# Thunder-Refix.net
KiCad netlist of a schematic drawn in Altium Designer
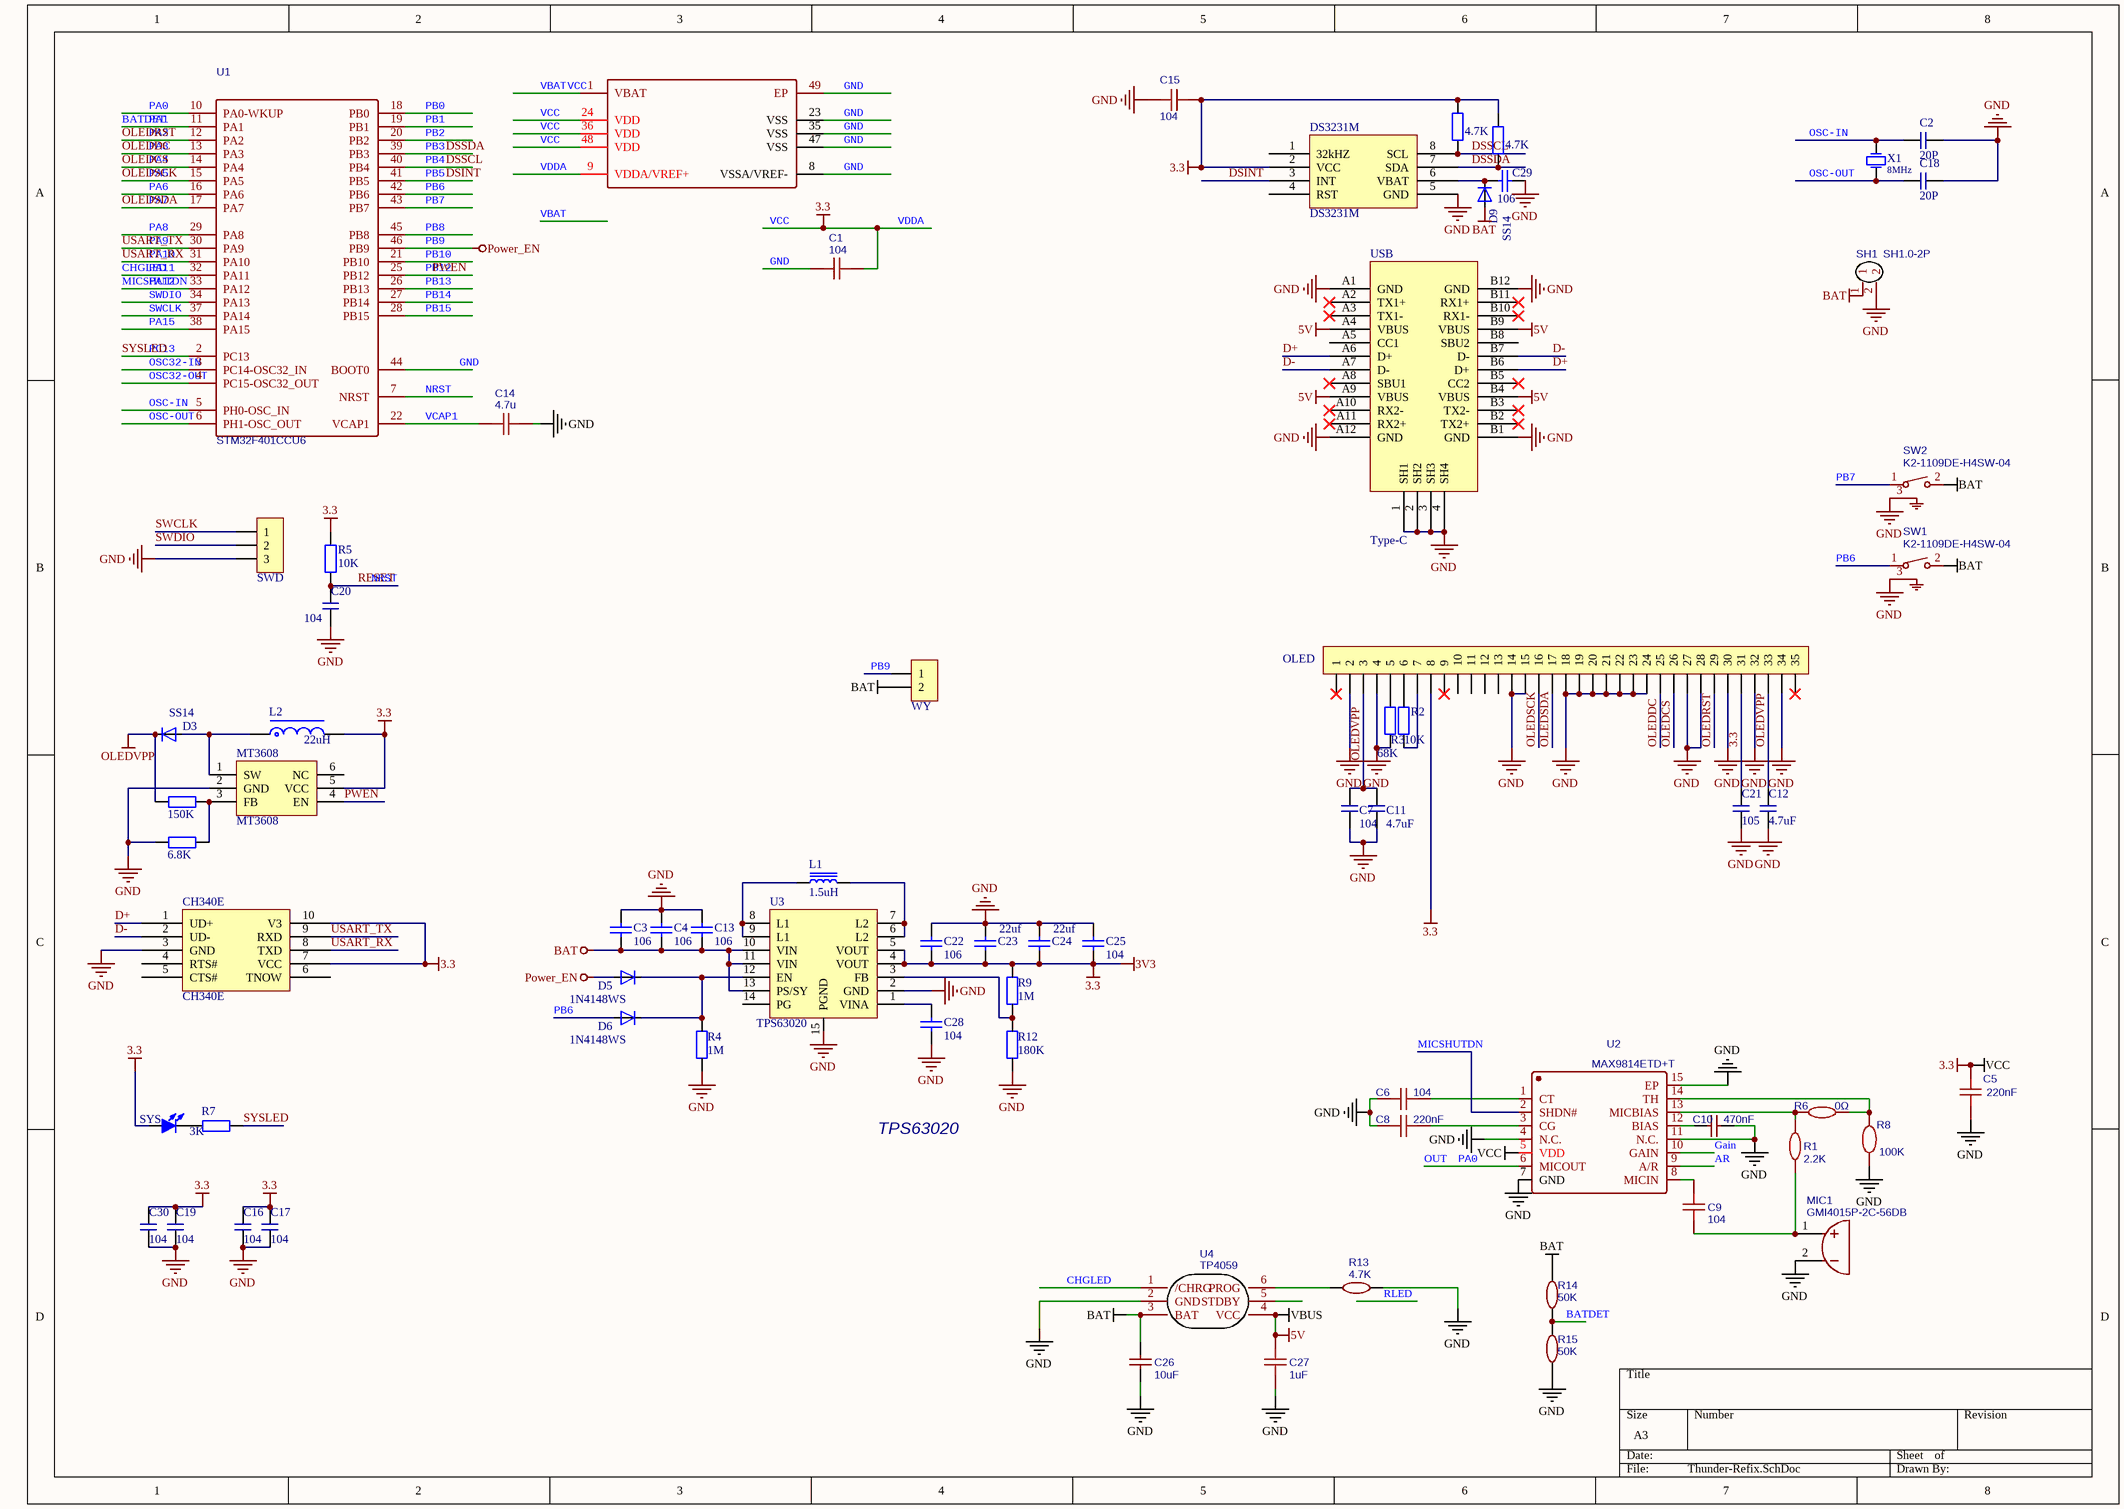
[diagram p0: Thunder-Refix.SchDoc]

(export (version "E")
  (design (tool "Eeschema 10.0.6"))
  (components
    (comp (ref "C1")
      (value "104")
      (footprint "0603C")
      (fields (field (name "CONTRIBUTOR") "LCEDA_Lib"))
      (libsource (lib "altium-import") (part "root_2_0.1u_"))
    )
    (comp (ref "C2") (value "20P") (footprint "0603C") (libsource (lib "Schlib1") (part "电容")))
    (comp (ref "C3")
      (value "106")
      (footprint "我的PCB库:0603c")
      (fields (field (name "C") "106"))
      (libsource (lib "元件库") (part "cap"))
    )
    (comp (ref "C4")
      (value "106")
      (footprint "我的PCB库:0603c")
      (fields (field (name "C") "106"))
      (libsource (lib "元件库") (part "cap"))
    )
    (comp (ref "C5")
      (value "220nF")
      (footprint "0603c")
      (fields
        (field (name "BOM_SUPPLIER PART") "C354366")
        (field (name "BOM_MANUFACTURER PART") "GCJ21BR71H224KA01L")
        (field (name "CONTRIBUTOR") "LCSC")
      )
      (libsource (lib "altium-import") (part "root_1_220nF_"))
    )
    (comp (ref "C6")
      (value "104")
      (footprint "0603c")
      (fields
        (field (name "BOM_SUPPLIER PART") "C444732")
        (field (name "BOM_MANUFACTURER PART") "FS055C104K4Z2A")
        (field (name "CONTRIBUTOR") "LCSC")
      )
      (libsource (lib "altium-import") (part "root_1_100nF_"))
    )
    (comp (ref "C7") (value "104") (footprint "0603C") (libsource (lib "Schlib1") (part "电容")))
    (comp (ref "C8")
      (value "220nF")
      (footprint "0603c")
      (fields
        (field (name "BOM_SUPPLIER PART") "C354366")
        (field (name "BOM_MANUFACTURER PART") "GCJ21BR71H224KA01L")
        (field (name "CONTRIBUTOR") "LCSC")
      )
      (libsource (lib "altium-import") (part "root_0_220nF_"))
    )
    (comp (ref "C9")
      (value "104")
      (footprint "0603c")
      (fields
        (field (name "BOM_SUPPLIER PART") "C444732")
        (field (name "BOM_MANUFACTURER PART") "FS055C104K4Z2A")
        (field (name "CONTRIBUTOR") "LCSC")
      )
      (libsource (lib "altium-import") (part "root_0_100nF_"))
    )
    (comp (ref "C10")
      (value "470nF")
      (footprint "0603c")
      (fields
        (field (name "BOM_MANUFACTURER PART") "CL21B474KBFNNNE")
        (field (name "BOM_SUPPLIER PART") "C13967")
      )
      (libsource (lib "altium-import") (part "root_0_470nF_"))
    )
    (comp (ref "C11") (value "4.7uF") (footprint "0603C") (libsource (lib "Schlib1") (part "电容")))
    (comp (ref "C12") (value "4.7uF") (footprint "0603C") (libsource (lib "Schlib1") (part "电容")))
    (comp (ref "C13")
      (value "106")
      (footprint "0603c")
      (fields (field (name "C") "106"))
      (libsource (lib "元件库") (part "cap"))
    )
    (comp (ref "C14")
      (value "4.7u")
      (footprint "0603C")
      (fields (field (name "CONTRIBUTOR") "LCEDA_Lib"))
      (libsource (lib "altium-import") (part "root_0_4.7u_"))
    )
    (comp (ref "C15")
      (value "104")
      (footprint "0603C")
      (fields (field (name "CONTRIBUTOR") "LCEDA_Lib"))
      (libsource (lib "altium-import") (part "root_2_0.1u_"))
    )
    (comp (ref "C16") (value "104") (footprint "0603C") (libsource (lib "Schlib1") (part "电容")))
    (comp (ref "C17") (value "104") (footprint "0603C") (libsource (lib "Schlib1") (part "电容")))
    (comp (ref "C18") (value "20P") (footprint "0603C") (libsource (lib "Schlib1") (part "电容")))
    (comp (ref "C19") (value "104") (footprint "0603C") (libsource (lib "Schlib1") (part "电容")))
    (comp (ref "C20") (value "104") (footprint "0603C") (libsource (lib "Schlib1") (part "电容")))
    (comp (ref "C21") (value "105") (footprint "0603C") (libsource (lib "Schlib1") (part "电容")))
    (comp (ref "C22")
      (value "106")
      (footprint "0603c")
      (fields (field (name "C") "106"))
      (libsource (lib "元件库") (part "cap"))
    )
    (comp (ref "C23")
      (value "22uf")
      (footprint "0603c")
      (fields (field (name "C") "22uf"))
      (libsource (lib "元件库") (part "cap"))
    )
    (comp (ref "C24")
      (value "22uf")
      (footprint "0603c")
      (fields (field (name "C") "22uf"))
      (libsource (lib "元件库") (part "cap"))
    )
    (comp (ref "C25")
      (value "104")
      (footprint "0603c")
      (fields (field (name "C") "104"))
      (libsource (lib "元件库") (part "cap"))
    )
    (comp (ref "C26")
      (value "10uF")
      (footprint "0603c")
      (fields
        (field (name "BOM_SUPPLIER PART") "C162317")
        (field (name "BOM_MANUFACTURER PART") "GRM21BB31C106KE15L")
        (field (name "CONTRIBUTOR") "LCSC")
      )
      (libsource (lib "altium-import") (part "root_1_10uF_"))
    )
    (comp (ref "C27")
      (value "1uF")
      (footprint "0603c")
      (fields
        (field (name "BOM_SUPPLIER PART") "C319195")
        (field (name "BOM_MANUFACTURER PART") "UMK212BJ105KG-T")
        (field (name "CONTRIBUTOR") "LCSC")
      )
      (libsource (lib "altium-import") (part "root_1_1uF_"))
    )
    (comp (ref "C28")
      (value "104")
      (footprint "0603c")
      (fields (field (name "C") "104"))
      (libsource (lib "元件库") (part "cap"))
    )
    (comp (ref "C29")
      (value "106")
      (footprint "0603c")
      (fields (field (name "C") "106"))
      (libsource (lib "元件库") (part "cap"))
    )
    (comp (ref "C30") (value "104") (footprint "0603C") (libsource (lib "Schlib1") (part "电容")))
    (comp (ref "CH340E") (value "CH340E") (footprint "MSOP10_L") (libsource (lib "CUBE_T1") (part "CH340E")))
    (comp (ref "D3")
      (value "SS14")
      (footprint "SOD323_1N4148WS")
      (description "Diode Switching 75V 0.3A 2-Pin SOD-323 T/R")
      (fields (field (name "MF") "ON Semiconductor") (field (name "MP") "1N4148WS"))
      (libsource (lib "1N4148WS") (part "1N4148WS"))
    )
    (comp (ref "D5")
      (value "1N4148WS")
      (footprint "SOD323_1N4148WS")
      (description "Diode Switching 75V 0.3A 2-Pin SOD-323 T/R")
      (fields (field (name "MF") "ON Semiconductor"))
      (libsource (lib "1N4148WS") (part "1N4148WS"))
    )
    (comp (ref "D6")
      (value "1N4148WS")
      (footprint "SOD323_1N4148WS")
      (description "Diode Switching 75V 0.3A 2-Pin SOD-323 T/R")
      (fields (field (name "MF") "ON Semiconductor"))
      (libsource (lib "1N4148WS") (part "1N4148WS"))
    )
    (comp (ref "D9")
      (value "SS14")
      (footprint "SOD323_1N4148WS")
      (description "Diode Switching 75V 0.3A 2-Pin SOD-323 T/R")
      (fields (field (name "MF") "ON Semiconductor") (field (name "MP") "1N4148WS"))
      (libsource (lib "1N4148WS") (part "1N4148WS"))
    )
    (comp (ref "DS3231M") (value "DS3231M") (footprint "SOP8") (libsource (lib "CUBE_T1") (part "DS3231M")))
    (comp (ref "L1")
      (value "1.5uH")
      (footprint "我的PCB库:IND-SMD_L3.0-W3.0_NR3010")
      (fields (field (name "_VALUE") "1.5uH"))
      (libsource (lib "元件库") (part "Inductor Iron 2"))
    )
    (comp (ref "L2")
      (value "22uH")
      (footprint "IND-SMD_L3.0-W3.0_NR3010")
      (description "功率屏蔽电感")
      (fields (field (name "版权归属") "源创客"))
      (libsource (lib "3.1   - 电阻-电容-电感") (part "L-CDRH"))
    )
    (comp (ref "MIC1")
      (value "GMI4015P-2C-56DB")
      (footprint "MIC-TH_BD4.0-P2.00-D0.4-L-FD")
      (fields
        (field (name "BOM_SUPPLIER PART") "C233299")
        (field (name "BOM_MANUFACTURER PART") "GMI4015P-2C-56db")
        (field (name "CONTRIBUTOR") "LCSC")
      )
      (libsource (lib "altium-import") (part "root_0_GMI4015P-2C-56DB_"))
    )
    (comp (ref "MT3608")
      (value "MT3608")
      (footprint "SOT23-6N")
      (description "可调升压芯片")
      (fields (field (name "版权归属") "源创客"))
      (libsource (lib "1.3   - 电源类芯片") (part "SX1308"))
    )
    (comp (ref "OLED")
      (value "FPC1.0-35P")
      (footprint "1.69 OLED")
      (description "FPC连接器")
      (fields (field (name "版权归属") "源创客"))
      (libsource (lib "4.14 - FPC连接器") (part "FPC-35P"))
    )
    (comp (ref "R1")
      (value "2.2K")
      (footprint "0603r")
      (fields
        (field (name "BOM_SUPPLIER PART") "C325769")
        (field (name "BOM_MANUFACTURER PART") "RMC08052.2K1%N")
        (field (name "CONTRIBUTOR") "LCSC")
      )
      (libsource (lib "altium-import") (part "root_1_2.2K_"))
    )
    (comp (ref "R2")
      (value "10K")
      (footprint "0603R")
      (description "贴片电阻")
      (fields (field (name "版权归属") "源创客"))
      (libsource (lib "3.1   - 电阻-电容-电感") (part "R"))
    )
    (comp (ref "R3")
      (value "68K")
      (footprint "0603R")
      (description "贴片电阻")
      (fields (field (name "版权归属") "源创客"))
      (libsource (lib "3.1   - 电阻-电容-电感") (part "R"))
    )
    (comp (ref "R4")
      (value "1M")
      (footprint "0603r")
      (fields (field (name "R") "1M"))
      (libsource (lib "元件库") (part "Res"))
    )
    (comp (ref "R5")
      (value "10K")
      (footprint "0603R")
      (description "贴片电阻")
      (fields (field (name "版权归属") "源创客"))
      (libsource (lib "3.1   - 电阻-电容-电感") (part "R"))
    )
    (comp (ref "R6")
      (value "0Ω")
      (footprint "0603r")
      (fields
        (field (name "BOM_SUPPLIER PART") "C325765")
        (field (name "BOM_MANUFACTURER PART") "RMC0805150K1%N")
        (field (name "CONTRIBUTOR") "LCSC")
      )
      (libsource (lib "altium-import") (part "root_0_150K_"))
    )
    (comp (ref "R7")
      (value "3K")
      (footprint "0603R")
      (description "贴片电阻")
      (fields (field (name "版权归属") "源创客"))
      (libsource (lib "3.1   - 电阻-电容-电感") (part "R"))
    )
    (comp (ref "R8")
      (value "100K")
      (footprint "0603r")
      (fields
        (field (name "BOM_SUPPLIER PART") "C346756")
        (field (name "BOM_MANUFACTURER PART") "RTAN0805BKE100K")
        (field (name "CONTRIBUTOR") "LCSC")
      )
      (libsource (lib "altium-import") (part "root_1_100K_"))
    )
    (comp (ref "R9")
      (value "1M")
      (footprint "0603r")
      (fields (field (name "R") "1M"))
      (libsource (lib "元件库") (part "Res"))
    )
    (comp (ref "R10")
      (value "4.7K")
      (footprint "0603R")
      (description "贴片电阻")
      (fields (field (name "版权归属") "源创客"))
      (libsource (lib "3.1   - 电阻-电容-电感") (part "R"))
    )
    (comp (ref "R11")
      (value "4.7K")
      (footprint "0603R")
      (description "贴片电阻")
      (fields (field (name "版权归属") "源创客"))
      (libsource (lib "3.1   - 电阻-电容-电感") (part "R"))
    )
    (comp (ref "R12")
      (value "180K")
      (footprint "0603r")
      (fields (field (name "R") "180K"))
      (libsource (lib "元件库") (part "Res"))
    )
    (comp (ref "R13")
      (value "4.7K")
      (footprint "0603r")
      (fields
        (field (name "BOM_MANUFACTURER PART") "RC0603FR-071K5L")
        (field (name "BOM_SUPPLIER PART") "C114668")
      )
      (libsource (lib "altium-import") (part "root_0_1.5K_"))
    )
    (comp (ref "R14")
      (value "50K")
      (footprint "0603r")
      (fields
        (field (name "BOM_MANUFACTURER PART") "RC0603FR-071K5L")
        (field (name "BOM_SUPPLIER PART") "C114668")
      )
      (libsource (lib "altium-import") (part "root_1_1.5K_"))
    )
    (comp (ref "R15")
      (value "50K")
      (footprint "0603r")
      (fields
        (field (name "BOM_MANUFACTURER PART") "RC0603FR-071K5L")
        (field (name "BOM_SUPPLIER PART") "C114668")
      )
      (libsource (lib "altium-import") (part "root_1_1.5K_"))
    )
    (comp (ref "RB")
      (value "150K")
      (footprint "0603R")
      (description "贴片电阻")
      (fields (field (name "版权归属") "源创客"))
      (libsource (lib "3.1   - 电阻-电容-电感") (part "R"))
    )
    (comp (ref "RS")
      (value "6.8K")
      (footprint "0603R")
      (description "贴片电阻")
      (fields (field (name "版权归属") "源创客"))
      (libsource (lib "3.1   - 电阻-电容-电感") (part "R"))
    )
    (comp (ref "SH1")
      (value "SH1.0-2P")
      (footprint "SH1.0-2P")
      (fields (field (name "CONTRIBUTOR") "perry2867"))
      (libsource (lib "altium-import") (part "root_1_SH1.0-2P_"))
    )
    (comp (ref "SW1")
      (value "K2-1109DE-H4SW-04")
      (footprint "KEY-TH_K2-1109DE-CXXW-XX")
      (fields (field (name "BOM_SUPPLIER PART") "C961730") (field (name "CONTRIBUTOR") "LCSC"))
      (libsource (lib "altium-import") (part "root_0_K2-1109DE-H4SW-04_"))
    )
    (comp (ref "SW2")
      (value "K2-1109DE-H4SW-04")
      (footprint "KEY-TH_K2-1109DE-CXXW-XX")
      (fields (field (name "BOM_SUPPLIER PART") "C961730") (field (name "CONTRIBUTOR") "LCSC"))
      (libsource (lib "altium-import") (part "root_0_K2-1109DE-H4SW-04_"))
    )
    (comp (ref "SWD")
      (value "HDR-1X3")
      (footprint "ZH1.5-LI-3P")
      (description "3P接插件")
      (fields (field (name "版权归属") "源创客"))
      (libsource (lib "4.3   - 接插件-脚距1.5") (part "Header 3"))
    )
    (comp (ref "SYS")
      (value "粉色")
      (footprint "0603LED")
      (description "方形LED")
      (fields (field (name "版权归属") "源创客"))
      (libsource (lib "9.1   - LED") (part "LED-F234"))
    )
    (comp (ref "U1")
      (value "STM32F401CCU6")
      (footprint "qfn48")
      (fields (field (name "BOM_SUPPLIER PART") "C79861") (field (name "SUBPART_NO") "1"))
      (libsource (lib "Galaxy") (part "STM32F401CCU6"))
    )
    (comp (ref "U2")
      (value "MAX9814ETD+T")
      (footprint "TDFN-14_L3.0-W3.0-P0.40-BL-EP")
      (fields (field (name "BOM_SUPPLIER PART") "C41714"))
      (libsource (lib "altium-import") (part "root_0_MAX9814ETD+T_"))
    )
    (comp (ref "U3")
      (value "TPS63020")
      (footprint "我的PCB库:TPS63020")
      (libsource (lib "我的元件库") (part "TPS63020"))
    )
    (comp (ref "U4")
      (value "TP4059")
      (footprint "SOT23-6N")
      (fields (field (name "BOM_SUPPLIER PART") "C80364"))
      (libsource (lib "altium-import") (part "root_0_TP4059_"))
    )
    (comp (ref "USB") (value "Type-C") (footprint "Type-C") (libsource (lib "元件") (part "Type-C")))
    (comp (ref "WY")
      (value "HDR-1X2")
      (footprint "MX 1.25-WI-2P")
      (description "2P接插件")
      (fields (field (name "版权归属") "源创客"))
      (libsource (lib "4.2   - 接插件-脚距1.25") (part "Header 2"))
    )
    (comp (ref "X1")
      (value "8MHz")
      (footprint "OSC 5032-2P")
      (description "XTAL,8MHz,±20PPM,12.6*4.5")
      (fields (field (name "Comment") "1.6.1.01.005.001"))
      (libsource (lib "Mark_7") (part "1.6.1.01.005.001"))
    )
  )
  (nets
    (net (code "1") (name "/AR") (class "Default")
      (node (ref "U2") (pin "9") (pinfunction "A/R_9") (pintype "passive"))
    )
    (net (code "2") (name "/BATDET") (class "Default")
      (node (ref "R14") (pin "1") (pinfunction "1_1") (pintype "passive"))
      (node (ref "R15") (pin "2") (pinfunction "2_2") (pintype "passive"))
      (node (ref "U1") (pin "11") (pinfunction "PA1_11") (pintype "passive"))
    )
    (net (code "3") (name "/CHGLED") (class "Default")
      (node (ref "U1") (pin "32") (pinfunction "PA11_32") (pintype "passive"))
      (node (ref "U4") (pin "1") (pinfunction "/CHRG_1") (pintype "passive"))
    )
    (net (code "4") (name "/D+") (class "Default")
      (node (ref "CH340E") (pin "1") (pinfunction "UD+_1") (pintype "passive"))
      (node (ref "USB") (pin "A6") (pinfunction "D+_A6") (pintype "passive"))
      (node (ref "USB") (pin "B6") (pinfunction "D+_B6") (pintype "passive"))
    )
    (net (code "5") (name "/D-") (class "Default")
      (node (ref "CH340E") (pin "2") (pinfunction "UD-_2") (pintype "passive"))
      (node (ref "USB") (pin "A7") (pinfunction "D-_A7") (pintype "passive"))
      (node (ref "USB") (pin "B7") (pinfunction "D-_B7") (pintype "passive"))
    )
    (net (code "6") (name "/DSINT") (class "Default")
      (node (ref "DS3231M") (pin "3") (pinfunction "INT_3") (pintype "passive"))
      (node (ref "U1") (pin "41") (pinfunction "PB5_41") (pintype "passive"))
    )
    (net (code "7") (name "/DSSCL") (class "Default")
      (node (ref "DS3231M") (pin "8") (pinfunction "SCL_8") (pintype "passive"))
      (node (ref "R10") (pin "2") (pinfunction "2_2") (pintype "passive"))
      (node (ref "U1") (pin "40") (pinfunction "PB4_40") (pintype "passive"))
    )
    (net (code "8") (name "/DSSDA") (class "Default")
      (node (ref "DS3231M") (pin "7") (pinfunction "SDA_7") (pintype "passive"))
      (node (ref "R11") (pin "2") (pinfunction "2_2") (pintype "passive"))
      (node (ref "U1") (pin "39") (pinfunction "PB3_39") (pintype "passive"))
    )
    (net (code "9") (name "/Gain") (class "Default")
      (node (ref "U2") (pin "10") (pinfunction "GAIN_10") (pintype "passive"))
    )
    (net (code "10") (name "/MICSHUTDN") (class "Default")
      (node (ref "U1") (pin "33") (pinfunction "PA12_33") (pintype "passive"))
      (node (ref "U2") (pin "2") (pinfunction "SHDN#_2") (pintype "passive"))
    )
    (net (code "11") (name "/NRST") (class "Default")
      (node (ref "C20") (pin "1") (pinfunction "1_1") (pintype "passive"))
      (node (ref "R5") (pin "2") (pinfunction "2_2") (pintype "passive"))
      (node (ref "U1") (pin "7") (pinfunction "NRST_7") (pintype "passive"))
    )
    (net (code "12") (name "/OLEDCS") (class "Default")
      (node (ref "OLED") (pin "26") (pinfunction "26_26") (pintype "passive"))
      (node (ref "U1") (pin "14") (pinfunction "PA4_14") (pintype "passive"))
    )
    (net (code "13") (name "/OLEDDC") (class "Default")
      (node (ref "OLED") (pin "25") (pinfunction "25_25") (pintype "passive"))
      (node (ref "U1") (pin "13") (pinfunction "PA3_13") (pintype "passive"))
    )
    (net (code "14") (name "/OLEDRST") (class "Default")
      (node (ref "OLED") (pin "29") (pinfunction "29_29") (pintype "passive"))
      (node (ref "U1") (pin "12") (pinfunction "PA2_12") (pintype "passive"))
    )
    (net (code "15") (name "/OLEDSCK") (class "Default")
      (node (ref "OLED") (pin "16") (pinfunction "16_16") (pintype "passive"))
      (node (ref "U1") (pin "15") (pinfunction "PA5_15") (pintype "passive"))
    )
    (net (code "16") (name "/OLEDSDA") (class "Default")
      (node (ref "OLED") (pin "17") (pinfunction "17_17") (pintype "passive"))
      (node (ref "U1") (pin "17") (pinfunction "PA7_17") (pintype "passive"))
    )
    (net (code "17") (name "/OSC-IN") (class "Default")
      (node (ref "C2") (pin "2") (pinfunction "2_2") (pintype "passive"))
      (node (ref "U1") (pin "5") (pinfunction "PH0-OSC_IN_5") (pintype "passive"))
      (node (ref "X1") (pin "1") (pinfunction "OSC1_1") (pintype "passive"))
    )
    (net (code "18") (name "/OSC-OUT") (class "Default")
      (node (ref "C18") (pin "2") (pinfunction "2_2") (pintype "passive"))
      (node (ref "U1") (pin "6") (pinfunction "PH1-OSC_OUT_6") (pintype "passive"))
      (node (ref "X1") (pin "2") (pinfunction "OSC2_2") (pintype "passive"))
    )
    (net (code "19") (name "/OSC32-IN") (class "Default")
      (node (ref "U1") (pin "3") (pinfunction "PC14-OSC32_IN_3") (pintype "passive"))
    )
    (net (code "20") (name "/OSC32-OUT") (class "Default")
      (node (ref "U1") (pin "4") (pinfunction "PC15-OSC32_OUT_4") (pintype "passive"))
    )
    (net (code "21") (name "/OUT") (class "Default")
      (node (ref "U1") (pin "10") (pinfunction "PA0-WKUP_10") (pintype "passive"))
      (node (ref "U2") (pin "6") (pinfunction "MICOUT_6") (pintype "passive"))
    )
    (net (code "22") (name "/PA6") (class "Default")
      (node (ref "U1") (pin "16") (pinfunction "PA6_16") (pintype "passive"))
    )
    (net (code "23") (name "/PA8") (class "Default")
      (node (ref "U1") (pin "29") (pinfunction "PA8_29") (pintype "passive"))
    )
    (net (code "24") (name "/PA9") (class "Default")
      (node (ref "CH340E") (pin "9") (pinfunction "RXD_9") (pintype "passive"))
      (node (ref "U1") (pin "30") (pinfunction "PA9_30") (pintype "passive"))
    )
    (net (code "25") (name "/PA10") (class "Default")
      (node (ref "CH340E") (pin "8") (pinfunction "TXD_8") (pintype "passive"))
      (node (ref "U1") (pin "31") (pinfunction "PA10_31") (pintype "passive"))
    )
    (net (code "26") (name "/PA15") (class "Default")
      (node (ref "U1") (pin "38") (pinfunction "PA15_38") (pintype "passive"))
    )
    (net (code "27") (name "/PB0") (class "Default")
      (node (ref "U1") (pin "18") (pinfunction "PB0_18") (pintype "passive"))
    )
    (net (code "28") (name "/PB1") (class "Default")
      (node (ref "U1") (pin "19") (pinfunction "PB1_19") (pintype "passive"))
    )
    (net (code "29") (name "/PB2") (class "Default")
      (node (ref "U1") (pin "20") (pinfunction "PB2_20") (pintype "passive"))
    )
    (net (code "30") (name "/PB6") (class "Default")
      (node (ref "D6") (pin "A") (pinfunction "A_A") (pintype "passive"))
      (node (ref "SW1") (pin "1") (pinfunction "1_1") (pintype "passive"))
      (node (ref "U1") (pin "42") (pinfunction "PB6_42") (pintype "passive"))
    )
    (net (code "31") (name "/PB7") (class "Default")
      (node (ref "SW2") (pin "1") (pinfunction "1_1") (pintype "passive"))
      (node (ref "U1") (pin "43") (pinfunction "PB7_43") (pintype "passive"))
    )
    (net (code "32") (name "/PB8") (class "Default")
      (node (ref "U1") (pin "45") (pinfunction "PB8_45") (pintype "passive"))
    )
    (net (code "33") (name "/PB10") (class "Default")
      (node (ref "U1") (pin "21") (pinfunction "PB10_21") (pintype "passive"))
    )
    (net (code "34") (name "/PB12") (class "Default")
      (node (ref "MT3608") (pin "4") (pinfunction "EN_4") (pintype "passive"))
      (node (ref "U1") (pin "25") (pinfunction "PB12_25") (pintype "passive"))
    )
    (net (code "35") (name "/PB13") (class "Default")
      (node (ref "U1") (pin "26") (pinfunction "PB13_26") (pintype "passive"))
    )
    (net (code "36") (name "/PB14") (class "Default")
      (node (ref "U1") (pin "27") (pinfunction "PB14_27") (pintype "passive"))
    )
    (net (code "37") (name "/PB15") (class "Default")
      (node (ref "U1") (pin "28") (pinfunction "PB15_28") (pintype "passive"))
    )
    (net (code "38") (name "/PC13") (class "Default")
      (node (ref "R7") (pin "1") (pinfunction "1_1") (pintype "passive"))
      (node (ref "U1") (pin "2") (pinfunction "PC13_2") (pintype "passive"))
    )
    (net (code "40") (name "/SWCLK") (class "Default")
      (node (ref "SWD") (pin "1") (pinfunction "1_1") (pintype "passive"))
      (node (ref "U1") (pin "37") (pinfunction "PA14_37") (pintype "passive"))
    )
    (net (code "41") (name "/SWDIO") (class "Default")
      (node (ref "SWD") (pin "2") (pinfunction "2_2") (pintype "passive"))
      (node (ref "U1") (pin "34") (pinfunction "PA13_34") (pintype "passive"))
    )
    (net (code "42") (name "/VCAP1") (class "Default")
      (node (ref "C14") (pin "1") (pinfunction "1_1") (pintype "passive"))
      (node (ref "U1") (pin "22") (pinfunction "VCAP1_22") (pintype "passive"))
    )
    (net (code "43") (name "3.3") (class "Default")
      (node (ref "C1") (pin "1") (pinfunction "1_1") (pintype "passive"))
      (node (ref "C15") (pin "1") (pinfunction "1_1") (pintype "passive"))
      (node (ref "C16") (pin "1") (pinfunction "1_1") (pintype "passive"))
      (node (ref "C17") (pin "1") (pinfunction "1_1") (pintype "passive"))
      (node (ref "C19") (pin "1") (pinfunction "1_1") (pintype "passive"))
      (node (ref "C21") (pin "1") (pinfunction "1_1") (pintype "passive"))
      (node (ref "C22") (pin "1") (pinfunction "1_1") (pintype "passive"))
      (node (ref "C23") (pin "1") (pinfunction "1_1") (pintype "passive"))
      (node (ref "C24") (pin "1") (pinfunction "1_1") (pintype "passive"))
      (node (ref "C25") (pin "1") (pinfunction "1_1") (pintype "passive"))
      (node (ref "C30") (pin "1") (pinfunction "1_1") (pintype "passive"))
      (node (ref "C5") (pin "2") (pinfunction "2_2") (pintype "passive"))
      (node (ref "CH340E") (pin "10") (pinfunction "V3_10") (pintype "passive"))
      (node (ref "CH340E") (pin "7") (pinfunction "VCC_7") (pintype "passive"))
      (node (ref "DS3231M") (pin "2") (pinfunction "VCC_2") (pintype "passive"))
      (node (ref "L2") (pin "2") (pinfunction "2_2") (pintype "passive"))
      (node (ref "MT3608") (pin "5") (pinfunction "VCC_5") (pintype "passive"))
      (node (ref "OLED") (pin "31") (pinfunction "31_31") (pintype "passive"))
      (node (ref "OLED") (pin "8") (pinfunction "8_8") (pintype "passive"))
      (node (ref "R10") (pin "1") (pinfunction "1_1") (pintype "passive"))
      (node (ref "R11") (pin "1") (pinfunction "1_1") (pintype "passive"))
      (node (ref "R5") (pin "1") (pinfunction "1_1") (pintype "passive"))
      (node (ref "R9") (pin "1") (pinfunction "1_1") (pintype "passive"))
      (node (ref "SYS") (pin "1") (pinfunction "A_1") (pintype "passive"))
      (node (ref "U1") (pin "1") (pinfunction "VBAT_1") (pintype "passive"))
      (node (ref "U1") (pin "24") (pinfunction "VDD_24") (pintype "passive"))
      (node (ref "U1") (pin "36") (pinfunction "VDD_36") (pintype "passive"))
      (node (ref "U1") (pin "48") (pinfunction "VDD_48") (pintype "passive"))
      (node (ref "U1") (pin "9") (pinfunction "VDDA/VREF+_9") (pintype "passive"))
      (node (ref "U2") (pin "5") (pinfunction "VDD_5") (pintype "passive"))
      (node (ref "U3") (pin "4") (pinfunction "VOUT_4") (pintype "passive"))
      (node (ref "U3") (pin "5") (pinfunction "VOUT_5") (pintype "passive"))
    )
    (net (code "44") (name "5V") (class "Default")
      (node (ref "C27") (pin "1") (pinfunction "1_1") (pintype "passive"))
      (node (ref "U4") (pin "4") (pinfunction "VCC_4") (pintype "passive"))
      (node (ref "USB") (pin "A4") (pinfunction "VBUS_A4") (pintype "passive"))
      (node (ref "USB") (pin "A9") (pinfunction "VBUS_A9") (pintype "passive"))
      (node (ref "USB") (pin "B4") (pinfunction "VBUS_B4") (pintype "passive"))
      (node (ref "USB") (pin "B9") (pinfunction "VBUS_B9") (pintype "passive"))
    )
    (net (code "45") (name "BAT") (class "Default")
      (node (ref "C13") (pin "1") (pinfunction "1_1") (pintype "passive"))
      (node (ref "C26") (pin "2") (pinfunction "2_2") (pintype "passive"))
      (node (ref "C3") (pin "1") (pinfunction "1_1") (pintype "passive"))
      (node (ref "C4") (pin "1") (pinfunction "1_1") (pintype "passive"))
      (node (ref "D9") (pin "A") (pinfunction "A_A") (pintype "passive"))
      (node (ref "R14") (pin "2") (pinfunction "2_2") (pintype "passive"))
      (node (ref "SH1") (pin "1") (pinfunction "1_1") (pintype "passive"))
      (node (ref "SW1") (pin "2") (pinfunction "2_2") (pintype "passive"))
      (node (ref "SW2") (pin "2") (pinfunction "2_2") (pintype "passive"))
      (node (ref "U3") (pin "10") (pinfunction "VIN_10") (pintype "passive"))
      (node (ref "U3") (pin "11") (pinfunction "VIN_11") (pintype "passive"))
      (node (ref "U3") (pin "13") (pinfunction "PS/SY_13") (pintype "passive"))
      (node (ref "U4") (pin "3") (pinfunction "BAT_3") (pintype "passive"))
      (node (ref "WY") (pin "2") (pinfunction "2_2") (pintype "passive"))
    )
    (net (code "46") (name "GND") (class "Default")
      (node (ref "C1") (pin "2") (pinfunction "2_2") (pintype "passive"))
      (node (ref "C10") (pin "2") (pinfunction "2_2") (pintype "passive"))
      (node (ref "C11") (pin "2") (pinfunction "2_2") (pintype "passive"))
      (node (ref "C12") (pin "2") (pinfunction "2_2") (pintype "passive"))
      (node (ref "C13") (pin "2") (pinfunction "2_2") (pintype "passive"))
      (node (ref "C14") (pin "2") (pinfunction "2_2") (pintype "passive"))
      (node (ref "C15") (pin "2") (pinfunction "2_2") (pintype "passive"))
      (node (ref "C16") (pin "2") (pinfunction "2_2") (pintype "passive"))
      (node (ref "C17") (pin "2") (pinfunction "2_2") (pintype "passive"))
      (node (ref "C18") (pin "1") (pinfunction "1_1") (pintype "passive"))
      (node (ref "C19") (pin "2") (pinfunction "2_2") (pintype "passive"))
      (node (ref "C2") (pin "1") (pinfunction "1_1") (pintype "passive"))
      (node (ref "C20") (pin "2") (pinfunction "2_2") (pintype "passive"))
      (node (ref "C21") (pin "2") (pinfunction "2_2") (pintype "passive"))
      (node (ref "C22") (pin "2") (pinfunction "2_2") (pintype "passive"))
      (node (ref "C23") (pin "2") (pinfunction "2_2") (pintype "passive"))
      (node (ref "C24") (pin "2") (pinfunction "2_2") (pintype "passive"))
      (node (ref "C25") (pin "2") (pinfunction "2_2") (pintype "passive"))
      (node (ref "C26") (pin "1") (pinfunction "1_1") (pintype "passive"))
      (node (ref "C27") (pin "2") (pinfunction "2_2") (pintype "passive"))
      (node (ref "C28") (pin "1") (pinfunction "1_1") (pintype "passive"))
      (node (ref "C29") (pin "1") (pinfunction "1_1") (pintype "passive"))
      (node (ref "C3") (pin "2") (pinfunction "2_2") (pintype "passive"))
      (node (ref "C30") (pin "2") (pinfunction "2_2") (pintype "passive"))
      (node (ref "C4") (pin "2") (pinfunction "2_2") (pintype "passive"))
      (node (ref "C5") (pin "1") (pinfunction "1_1") (pintype "passive"))
      (node (ref "C6") (pin "1") (pinfunction "1_1") (pintype "passive"))
      (node (ref "C7") (pin "2") (pinfunction "2_2") (pintype "passive"))
      (node (ref "C8") (pin "1") (pinfunction "1_1") (pintype "passive"))
      (node (ref "CH340E") (pin "3") (pinfunction "GND_3") (pintype "passive"))
      (node (ref "DS3231M") (pin "5") (pinfunction "GND_5") (pintype "passive"))
      (node (ref "MIC1") (pin "2") (pinfunction "2_2") (pintype "passive"))
      (node (ref "MT3608") (pin "2") (pinfunction "GND_2") (pintype "passive"))
      (node (ref "OLED") (pin "14") (pinfunction "14_14") (pintype "passive"))
      (node (ref "OLED") (pin "15") (pinfunction "15_15") (pintype "passive"))
      (node (ref "OLED") (pin "18") (pinfunction "18_18") (pintype "passive"))
      (node (ref "OLED") (pin "19") (pinfunction "19_19") (pintype "passive"))
      (node (ref "OLED") (pin "2") (pinfunction "2_2") (pintype "passive"))
      (node (ref "OLED") (pin "20") (pinfunction "20_20") (pintype "passive"))
      (node (ref "OLED") (pin "21") (pinfunction "21_21") (pintype "passive"))
      (node (ref "OLED") (pin "22") (pinfunction "22_22") (pintype "passive"))
      (node (ref "OLED") (pin "23") (pinfunction "23_23") (pintype "passive"))
      (node (ref "OLED") (pin "24") (pinfunction "24_24") (pintype "passive"))
      (node (ref "OLED") (pin "27") (pinfunction "27_27") (pintype "passive"))
      (node (ref "OLED") (pin "28") (pinfunction "28_28") (pintype "passive"))
      (node (ref "OLED") (pin "30") (pinfunction "30_30") (pintype "passive"))
      (node (ref "OLED") (pin "32") (pinfunction "32_32") (pintype "passive"))
      (node (ref "OLED") (pin "34") (pinfunction "34_34") (pintype "passive"))
      (node (ref "OLED") (pin "4") (pinfunction "4_4") (pintype "passive"))
      (node (ref "R12") (pin "2") (pinfunction "2_2") (pintype "passive"))
      (node (ref "R13") (pin "2") (pinfunction "2_2") (pintype "passive"))
      (node (ref "R15") (pin "1") (pinfunction "1_1") (pintype "passive"))
      (node (ref "R3") (pin "1") (pinfunction "1_1") (pintype "passive"))
      (node (ref "R4") (pin "2") (pinfunction "2_2") (pintype "passive"))
      (node (ref "R8") (pin "1") (pinfunction "1_1") (pintype "passive"))
      (node (ref "RS") (pin "1") (pinfunction "1_1") (pintype "passive"))
      (node (ref "SH1") (pin "2") (pinfunction "2_2") (pintype "passive"))
      (node (ref "SW1") (pin "3") (pinfunction "GND_3") (pintype "passive"))
      (node (ref "SW2") (pin "3") (pinfunction "GND_3") (pintype "passive"))
      (node (ref "SWD") (pin "3") (pinfunction "3_3") (pintype "passive"))
      (node (ref "U1") (pin "23") (pinfunction "VSS_23") (pintype "passive"))
      (node (ref "U1") (pin "35") (pinfunction "VSS_35") (pintype "passive"))
      (node (ref "U1") (pin "44") (pinfunction "BOOT0_44") (pintype "passive"))
      (node (ref "U1") (pin "47") (pinfunction "VSS_47") (pintype "passive"))
      (node (ref "U1") (pin "49") (pinfunction "EP_49") (pintype "passive"))
      (node (ref "U1") (pin "8") (pinfunction "VSSA/VREF-_8") (pintype "passive"))
      (node (ref "U2") (pin "11") (pinfunction "N.C._11") (pintype "passive"))
      (node (ref "U2") (pin "15") (pinfunction "EP_15") (pintype "passive"))
      (node (ref "U2") (pin "4") (pinfunction "N.C._4") (pintype "passive"))
      (node (ref "U2") (pin "7") (pinfunction "GND_7") (pintype "passive"))
      (node (ref "U3") (pin "15") (pinfunction "PGND_15") (pintype "passive"))
      (node (ref "U3") (pin "2") (pinfunction "GND_2") (pintype "passive"))
      (node (ref "U4") (pin "2") (pinfunction "GND_2") (pintype "passive"))
      (node (ref "USB") (pin "1") (pinfunction "SH1_1") (pintype "passive"))
      (node (ref "USB") (pin "2") (pinfunction "SH2_2") (pintype "passive"))
      (node (ref "USB") (pin "3") (pinfunction "SH3_3") (pintype "passive"))
      (node (ref "USB") (pin "4") (pinfunction "SH4_4") (pintype "passive"))
      (node (ref "USB") (pin "A1") (pinfunction "GND_A1") (pintype "passive"))
      (node (ref "USB") (pin "A12") (pinfunction "GND_A12") (pintype "passive"))
      (node (ref "USB") (pin "B1") (pinfunction "GND_B1") (pintype "passive"))
      (node (ref "USB") (pin "B12") (pinfunction "GND_B12") (pintype "passive"))
    )
    (net (code "47") (name "Net-(C9-Pad2)") (class "Default")
      (node (ref "C9") (pin "2") (pinfunction "2_2") (pintype "passive"))
      (node (ref "MIC1") (pin "1") (pinfunction "1_1") (pintype "passive"))
      (node (ref "R1") (pin "1") (pinfunction "1_1") (pintype "passive"))
    )
    (net (code "48") (name "Net-(DS3231M-VBAT)") (class "Default")
      (node (ref "C29") (pin "2") (pinfunction "2_2") (pintype "passive"))
      (node (ref "D9") (pin "C") (pinfunction "C_C") (pintype "passive"))
      (node (ref "DS3231M") (pin "6") (pinfunction "VBAT_6") (pintype "passive"))
    )
    (net (code "49") (name "Net-(L1-Pad1)") (class "Default")
      (node (ref "L1") (pin "1") (pinfunction "1_1") (pintype "passive"))
      (node (ref "U3") (pin "8") (pinfunction "L1_8") (pintype "passive"))
      (node (ref "U3") (pin "9") (pinfunction "L1_9") (pintype "passive"))
    )
    (net (code "50") (name "Net-(L1-Pad2)") (class "Default")
      (node (ref "L1") (pin "2") (pinfunction "2_2") (pintype "passive"))
      (node (ref "U3") (pin "6") (pinfunction "L2_6") (pintype "passive"))
      (node (ref "U3") (pin "7") (pinfunction "L2_7") (pintype "passive"))
    )
    (net (code "51") (name "Net-(MT3608-FB)") (class "Default")
      (node (ref "MT3608") (pin "3") (pinfunction "FB_3") (pintype "passive"))
      (node (ref "RB") (pin "2") (pinfunction "2_2") (pintype "passive"))
      (node (ref "RS") (pin "2") (pinfunction "2_2") (pintype "passive"))
    )
    (net (code "52") (name "Net-(MT3608-SW)") (class "Default")
      (node (ref "D3") (pin "A") (pinfunction "A_A") (pintype "passive"))
      (node (ref "L2") (pin "1") (pinfunction "1_1") (pintype "passive"))
      (node (ref "MT3608") (pin "1") (pinfunction "SW_1") (pintype "passive"))
    )
    (net (code "53") (name "Net-(OLED-Pad5)") (class "Default")
      (node (ref "OLED") (pin "5") (pinfunction "5_5") (pintype "passive"))
      (node (ref "R3") (pin "2") (pinfunction "2_2") (pintype "passive"))
    )
    (net (code "54") (name "Net-(OLED-Pad6)") (class "Default")
      (node (ref "OLED") (pin "6") (pinfunction "6_6") (pintype "passive"))
      (node (ref "R2") (pin "2") (pinfunction "2_2") (pintype "passive"))
    )
    (net (code "55") (name "Net-(OLED-Pad7)") (class "Default")
      (node (ref "OLED") (pin "7") (pinfunction "7_7") (pintype "passive"))
      (node (ref "R2") (pin "1") (pinfunction "1_1") (pintype "passive"))
    )
    (net (code "56") (name "Net-(SYS-K)") (class "Default")
      (node (ref "R7") (pin "2") (pinfunction "2_2") (pintype "passive"))
      (node (ref "SYS") (pin "2") (pinfunction "K_2") (pintype "passive"))
    )
    (net (code "57") (name "Net-(U2-BIAS)") (class "Default")
      (node (ref "C10") (pin "1") (pinfunction "1_1") (pintype "passive"))
      (node (ref "U2") (pin "12") (pinfunction "BIAS_12") (pintype "passive"))
    )
    (net (code "58") (name "Net-(U2-CG)") (class "Default")
      (node (ref "C8") (pin "2") (pinfunction "2_2") (pintype "passive"))
      (node (ref "U2") (pin "3") (pinfunction "CG_3") (pintype "passive"))
    )
    (net (code "59") (name "Net-(U2-CT)") (class "Default")
      (node (ref "C6") (pin "2") (pinfunction "2_2") (pintype "passive"))
      (node (ref "U2") (pin "1") (pinfunction "CT_1") (pintype "passive"))
    )
    (net (code "60") (name "Net-(U2-MICBIAS)") (class "Default")
      (node (ref "R1") (pin "2") (pinfunction "2_2") (pintype "passive"))
      (node (ref "R6") (pin "1") (pinfunction "1_1") (pintype "passive"))
      (node (ref "U2") (pin "13") (pinfunction "MICBIAS_13") (pintype "passive"))
    )
    (net (code "61") (name "Net-(U2-MICIN)") (class "Default")
      (node (ref "C9") (pin "1") (pinfunction "1_1") (pintype "passive"))
      (node (ref "U2") (pin "8") (pinfunction "MICIN_8") (pintype "passive"))
    )
    (net (code "62") (name "Net-(U2-TH)") (class "Default")
      (node (ref "R6") (pin "2") (pinfunction "2_2") (pintype "passive"))
      (node (ref "R8") (pin "2") (pinfunction "2_2") (pintype "passive"))
      (node (ref "U2") (pin "14") (pinfunction "TH_14") (pintype "passive"))
    )
    (net (code "63") (name "Net-(U3-EN)") (class "Default")
      (node (ref "D5") (pin "C") (pinfunction "C_C") (pintype "passive"))
      (node (ref "D6") (pin "C") (pinfunction "C_C") (pintype "passive"))
      (node (ref "R4") (pin "1") (pinfunction "1_1") (pintype "passive"))
      (node (ref "U3") (pin "12") (pinfunction "EN_12") (pintype "passive"))
    )
    (net (code "64") (name "Net-(U3-FB)") (class "Default")
      (node (ref "R12") (pin "1") (pinfunction "1_1") (pintype "passive"))
      (node (ref "R9") (pin "2") (pinfunction "2_2") (pintype "passive"))
      (node (ref "U3") (pin "3") (pinfunction "FB_3") (pintype "passive"))
    )
    (net (code "65") (name "Net-(U3-VINA)") (class "Default")
      (node (ref "C28") (pin "2") (pinfunction "2_2") (pintype "passive"))
      (node (ref "U3") (pin "1") (pinfunction "VINA_1") (pintype "passive"))
    )
    (net (code "66") (name "Net-(U4-PROG)") (class "Default")
      (node (ref "R13") (pin "1") (pinfunction "1_1") (pintype "passive"))
      (node (ref "U4") (pin "6") (pinfunction "PROG_6") (pintype "passive"))
    )
    (net (code "67") (name "OLEDVPP") (class "Default")
      (node (ref "C11") (pin "1") (pinfunction "1_1") (pintype "passive"))
      (node (ref "C12") (pin "1") (pinfunction "1_1") (pintype "passive"))
      (node (ref "C7") (pin "1") (pinfunction "1_1") (pintype "passive"))
      (node (ref "D3") (pin "C") (pinfunction "C_C") (pintype "passive"))
      (node (ref "OLED") (pin "3") (pinfunction "3_3") (pintype "passive"))
      (node (ref "OLED") (pin "33") (pinfunction "33_33") (pintype "passive"))
      (node (ref "RB") (pin "1") (pinfunction "1_1") (pintype "passive"))
    )
    (net (code "68") (name "Power_EN") (class "Default")
      (node (ref "D5") (pin "A") (pinfunction "A_A") (pintype "passive"))
      (node (ref "U1") (pin "46") (pinfunction "PB9_46") (pintype "passive"))
      (node (ref "WY") (pin "1") (pinfunction "1_1") (pintype "passive"))
    )
    (net (code "69") (name "unconnected-(CH340E-CTS#-Pad5)") (class "Default")
      (node (ref "CH340E") (pin "5") (pinfunction "CTS#_5") (pintype "passive"))
    )
    (net (code "70") (name "unconnected-(CH340E-RTS#-Pad4)") (class "Default")
      (node (ref "CH340E") (pin "4") (pinfunction "RTS#_4") (pintype "passive"))
    )
    (net (code "71") (name "unconnected-(CH340E-TNOW-Pad6)") (class "Default")
      (node (ref "CH340E") (pin "6") (pinfunction "TNOW_6") (pintype "passive"))
    )
    (net (code "72") (name "unconnected-(DS3231M-32kHZ-Pad1)") (class "Default")
      (node (ref "DS3231M") (pin "1") (pinfunction "32kHZ_1") (pintype "passive"))
    )
    (net (code "73") (name "unconnected-(DS3231M-RST-Pad4)") (class "Default")
      (node (ref "DS3231M") (pin "4") (pinfunction "RST_4") (pintype "passive"))
    )
    (net (code "74") (name "unconnected-(MT3608-NC-Pad6)") (class "Default")
      (node (ref "MT3608") (pin "6") (pinfunction "NC_6") (pintype "passive"))
    )
    (net (code "75") (name "unconnected-(OLED-Pad1)") (class "Default")
      (node (ref "OLED") (pin "1") (pinfunction "1_1") (pintype "passive+no_connect"))
    )
    (net (code "76") (name "unconnected-(OLED-Pad9)") (class "Default")
      (node (ref "OLED") (pin "9") (pinfunction "9_9") (pintype "passive+no_connect"))
    )
    (net (code "77") (name "unconnected-(OLED-Pad10)") (class "Default")
      (node (ref "OLED") (pin "10") (pinfunction "10_10") (pintype "passive"))
    )
    (net (code "78") (name "unconnected-(OLED-Pad11)") (class "Default")
      (node (ref "OLED") (pin "11") (pinfunction "11_11") (pintype "passive"))
    )
    (net (code "79") (name "unconnected-(OLED-Pad12)") (class "Default")
      (node (ref "OLED") (pin "12") (pinfunction "12_12") (pintype "passive"))
    )
    (net (code "80") (name "unconnected-(OLED-Pad13)") (class "Default")
      (node (ref "OLED") (pin "13") (pinfunction "13_13") (pintype "passive"))
    )
    (net (code "81") (name "unconnected-(OLED-Pad35)") (class "Default")
      (node (ref "OLED") (pin "35") (pinfunction "35_35") (pintype "passive+no_connect"))
    )
    (net (code "82") (name "unconnected-(U3-PG-Pad14)") (class "Default")
      (node (ref "U3") (pin "14") (pinfunction "PG_14") (pintype "passive"))
    )
    (net (code "83") (name "unconnected-(U4-STDBY-Pad5)") (class "Default")
      (node (ref "U4") (pin "5") (pinfunction "STDBY_5") (pintype "passive"))
    )
    (net (code "84") (name "unconnected-(USB-CC1-PadA5)") (class "Default")
      (node (ref "USB") (pin "A5") (pinfunction "CC1_A5") (pintype "passive"))
    )
    (net (code "85") (name "unconnected-(USB-CC2-PadB5)") (class "Default")
      (node (ref "USB") (pin "B5") (pinfunction "CC2_B5") (pintype "passive+no_connect"))
    )
    (net (code "86") (name "unconnected-(USB-RX1+-PadB11)") (class "Default")
      (node (ref "USB") (pin "B11") (pinfunction "RX1+_B11") (pintype "passive+no_connect"))
    )
    (net (code "87") (name "unconnected-(USB-RX1--PadB10)") (class "Default")
      (node (ref "USB") (pin "B10") (pinfunction "RX1-_B10") (pintype "passive+no_connect"))
    )
    (net (code "88") (name "unconnected-(USB-RX2+-PadA11)") (class "Default")
      (node (ref "USB") (pin "A11") (pinfunction "RX2+_A11") (pintype "passive+no_connect"))
    )
    (net (code "89") (name "unconnected-(USB-RX2--PadA10)") (class "Default")
      (node (ref "USB") (pin "A10") (pinfunction "RX2-_A10") (pintype "passive+no_connect"))
    )
    (net (code "90") (name "unconnected-(USB-SBU1-PadA8)") (class "Default")
      (node (ref "USB") (pin "A8") (pinfunction "SBU1_A8") (pintype "passive+no_connect"))
    )
    (net (code "91") (name "unconnected-(USB-SBU2-PadB8)") (class "Default")
      (node (ref "USB") (pin "B8") (pinfunction "SBU2_B8") (pintype "passive"))
    )
    (net (code "92") (name "unconnected-(USB-TX1+-PadA2)") (class "Default")
      (node (ref "USB") (pin "A2") (pinfunction "TX1+_A2") (pintype "passive+no_connect"))
    )
    (net (code "93") (name "unconnected-(USB-TX1--PadA3)") (class "Default")
      (node (ref "USB") (pin "A3") (pinfunction "TX1-_A3") (pintype "passive+no_connect"))
    )
    (net (code "94") (name "unconnected-(USB-TX2+-PadB2)") (class "Default")
      (node (ref "USB") (pin "B2") (pinfunction "TX2+_B2") (pintype "passive+no_connect"))
    )
    (net (code "95") (name "unconnected-(USB-TX2--PadB3)") (class "Default")
      (node (ref "USB") (pin "B3") (pinfunction "TX2-_B3") (pintype "passive+no_connect"))
    )
  )
)
